# lilygo-surf-v1.net
KiCad netlist of a schematic drawn in EAGLE
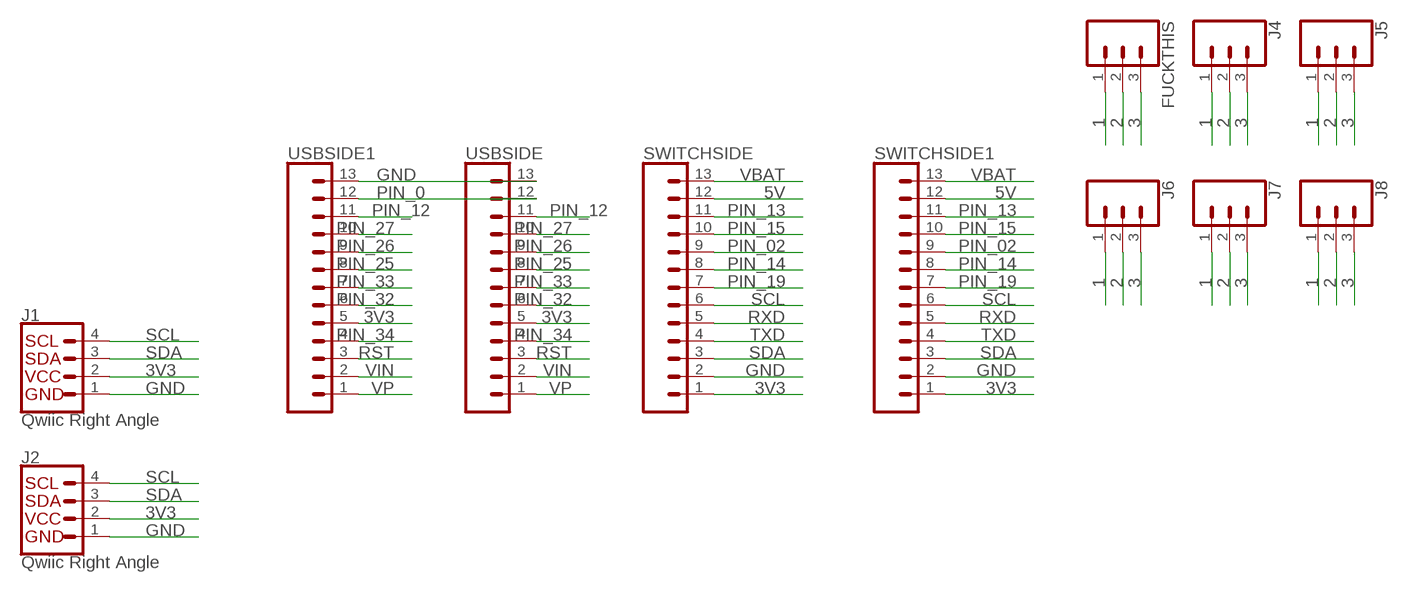
[diagram p0: schematic, sheet 1]

(export (version "E")
  (design (tool "Eeschema 10.0.6"))
  (components
    (comp (ref "FUCKTHIS")
      (value "CONN_03")
      (footprint "eagle-import:1X03")
      (libsource (lib "eagle-import") (part "CONN_03"))
    )
    (comp (ref "J1")
      (value "Qwiic Right Angle")
      (footprint "eagle-import:1X04_1MM_RA")
      (libsource (lib "eagle-import") (part "I2C_STANDARDQWIIC"))
    )
    (comp (ref "J2")
      (value "Qwiic Right Angle")
      (footprint "eagle-import:1X04_1MM_RA")
      (libsource (lib "eagle-import") (part "I2C_STANDARDQWIIC"))
    )
    (comp (ref "J4")
      (value "CONN_03")
      (footprint "eagle-import:1X03")
      (libsource (lib "eagle-import") (part "CONN_03"))
    )
    (comp (ref "J5")
      (value "CONN_03")
      (footprint "eagle-import:1X03")
      (libsource (lib "eagle-import") (part "CONN_03"))
    )
    (comp (ref "J6")
      (value "CONN_03")
      (footprint "eagle-import:1X03")
      (libsource (lib "eagle-import") (part "CONN_03"))
    )
    (comp (ref "J7")
      (value "CONN_03")
      (footprint "eagle-import:1X03")
      (libsource (lib "eagle-import") (part "CONN_03"))
    )
    (comp (ref "J8")
      (value "CONN_03")
      (footprint "eagle-import:1X03")
      (libsource (lib "eagle-import") (part "CONN_03"))
    )
    (comp (ref "SWITCHSIDE")
      (value "CONN_13LOCK")
      (footprint "eagle-import:1X13_LOCK")
      (libsource (lib "eagle-import") (part "CONN_13LOCK"))
    )
    (comp (ref "SWITCHSIDE1")
      (value "CONN_13LOCK")
      (footprint "eagle-import:1X13_LOCK")
      (libsource (lib "eagle-import") (part "CONN_13LOCK"))
    )
    (comp (ref "USBSIDE")
      (value "CONN_13LOCK")
      (footprint "eagle-import:1X13_LOCK")
      (libsource (lib "eagle-import") (part "CONN_13LOCK"))
    )
    (comp (ref "USBSIDE1")
      (value "CONN_13LOCK")
      (footprint "eagle-import:1X13_LOCK")
      (libsource (lib "eagle-import") (part "CONN_13LOCK"))
    )
  )
  (nets
    (net (code "1") (name "/1") (class "Default")
      (node (ref "FUCKTHIS") (pin "1") (pinfunction "1_1") (pintype "passive"))
      (node (ref "J4") (pin "1") (pinfunction "1_1") (pintype "passive"))
      (node (ref "J5") (pin "1") (pinfunction "1_1") (pintype "passive"))
      (node (ref "J6") (pin "1") (pinfunction "1_1") (pintype "passive"))
      (node (ref "J7") (pin "1") (pinfunction "1_1") (pintype "passive"))
      (node (ref "J8") (pin "1") (pinfunction "1_1") (pintype "passive"))
    )
    (net (code "2") (name "/2") (class "Default")
      (node (ref "FUCKTHIS") (pin "2") (pinfunction "2_2") (pintype "passive"))
      (node (ref "J4") (pin "2") (pinfunction "2_2") (pintype "passive"))
      (node (ref "J5") (pin "2") (pinfunction "2_2") (pintype "passive"))
      (node (ref "J6") (pin "2") (pinfunction "2_2") (pintype "passive"))
      (node (ref "J7") (pin "2") (pinfunction "2_2") (pintype "passive"))
      (node (ref "J8") (pin "2") (pinfunction "2_2") (pintype "passive"))
    )
    (net (code "3") (name "/3") (class "Default")
      (node (ref "FUCKTHIS") (pin "3") (pinfunction "3_3") (pintype "passive"))
      (node (ref "J4") (pin "3") (pinfunction "3_3") (pintype "passive"))
      (node (ref "J5") (pin "3") (pinfunction "3_3") (pintype "passive"))
      (node (ref "J6") (pin "3") (pinfunction "3_3") (pintype "passive"))
      (node (ref "J7") (pin "3") (pinfunction "3_3") (pintype "passive"))
      (node (ref "J8") (pin "3") (pinfunction "3_3") (pintype "passive"))
    )
    (net (code "4") (name "/3V3") (class "Default")
      (node (ref "J1") (pin "2") (pinfunction "2_2") (pintype "power_in"))
      (node (ref "J2") (pin "2") (pinfunction "2_2") (pintype "power_in"))
      (node (ref "SWITCHSIDE") (pin "1") (pinfunction "1_1") (pintype "passive"))
      (node (ref "SWITCHSIDE1") (pin "1") (pinfunction "1_1") (pintype "passive"))
      (node (ref "USBSIDE") (pin "5") (pinfunction "5_5") (pintype "passive"))
      (node (ref "USBSIDE1") (pin "5") (pinfunction "5_5") (pintype "passive"))
    )
    (net (code "5") (name "/5V") (class "Default")
      (node (ref "SWITCHSIDE") (pin "12") (pinfunction "12_12") (pintype "passive"))
      (node (ref "SWITCHSIDE1") (pin "12") (pinfunction "12_12") (pintype "passive"))
    )
    (net (code "6") (name "/GND") (class "Default")
      (node (ref "J1") (pin "1") (pinfunction "1_1") (pintype "power_in"))
      (node (ref "J2") (pin "1") (pinfunction "1_1") (pintype "power_in"))
      (node (ref "SWITCHSIDE") (pin "2") (pinfunction "2_2") (pintype "passive"))
      (node (ref "SWITCHSIDE1") (pin "2") (pinfunction "2_2") (pintype "passive"))
      (node (ref "USBSIDE") (pin "13") (pinfunction "13_13") (pintype "passive"))
      (node (ref "USBSIDE1") (pin "13") (pinfunction "13_13") (pintype "passive"))
    )
    (net (code "7") (name "/PIN_0") (class "Default")
      (node (ref "USBSIDE") (pin "12") (pinfunction "12_12") (pintype "passive"))
      (node (ref "USBSIDE1") (pin "12") (pinfunction "12_12") (pintype "passive"))
    )
    (net (code "8") (name "/PIN_02") (class "Default")
      (node (ref "SWITCHSIDE") (pin "9") (pinfunction "9_9") (pintype "passive"))
      (node (ref "SWITCHSIDE1") (pin "9") (pinfunction "9_9") (pintype "passive"))
    )
    (net (code "9") (name "/PIN_12") (class "Default")
      (node (ref "USBSIDE") (pin "11") (pinfunction "11_11") (pintype "passive"))
      (node (ref "USBSIDE1") (pin "11") (pinfunction "11_11") (pintype "passive"))
    )
    (net (code "10") (name "/PIN_13") (class "Default")
      (node (ref "SWITCHSIDE") (pin "11") (pinfunction "11_11") (pintype "passive"))
      (node (ref "SWITCHSIDE1") (pin "11") (pinfunction "11_11") (pintype "passive"))
    )
    (net (code "11") (name "/PIN_14") (class "Default")
      (node (ref "SWITCHSIDE") (pin "8") (pinfunction "8_8") (pintype "passive"))
      (node (ref "SWITCHSIDE1") (pin "8") (pinfunction "8_8") (pintype "passive"))
    )
    (net (code "12") (name "/PIN_15") (class "Default")
      (node (ref "SWITCHSIDE") (pin "10") (pinfunction "10_10") (pintype "passive"))
      (node (ref "SWITCHSIDE1") (pin "10") (pinfunction "10_10") (pintype "passive"))
    )
    (net (code "13") (name "/PIN_19") (class "Default")
      (node (ref "SWITCHSIDE") (pin "7") (pinfunction "7_7") (pintype "passive"))
      (node (ref "SWITCHSIDE1") (pin "7") (pinfunction "7_7") (pintype "passive"))
    )
    (net (code "14") (name "/PIN_25") (class "Default")
      (node (ref "USBSIDE") (pin "8") (pinfunction "8_8") (pintype "passive"))
      (node (ref "USBSIDE1") (pin "8") (pinfunction "8_8") (pintype "passive"))
    )
    (net (code "15") (name "/PIN_26") (class "Default")
      (node (ref "USBSIDE") (pin "9") (pinfunction "9_9") (pintype "passive"))
      (node (ref "USBSIDE1") (pin "9") (pinfunction "9_9") (pintype "passive"))
    )
    (net (code "16") (name "/PIN_27") (class "Default")
      (node (ref "USBSIDE") (pin "10") (pinfunction "10_10") (pintype "passive"))
      (node (ref "USBSIDE1") (pin "10") (pinfunction "10_10") (pintype "passive"))
    )
    (net (code "17") (name "/PIN_32") (class "Default")
      (node (ref "USBSIDE") (pin "6") (pinfunction "6_6") (pintype "passive"))
      (node (ref "USBSIDE1") (pin "6") (pinfunction "6_6") (pintype "passive"))
    )
    (net (code "18") (name "/PIN_33") (class "Default")
      (node (ref "USBSIDE") (pin "7") (pinfunction "7_7") (pintype "passive"))
      (node (ref "USBSIDE1") (pin "7") (pinfunction "7_7") (pintype "passive"))
    )
    (net (code "19") (name "/PIN_34") (class "Default")
      (node (ref "USBSIDE") (pin "4") (pinfunction "4_4") (pintype "passive"))
      (node (ref "USBSIDE1") (pin "4") (pinfunction "4_4") (pintype "passive"))
    )
    (net (code "20") (name "/RST") (class "Default")
      (node (ref "USBSIDE") (pin "3") (pinfunction "3_3") (pintype "passive"))
      (node (ref "USBSIDE1") (pin "3") (pinfunction "3_3") (pintype "passive"))
    )
    (net (code "21") (name "/RXD") (class "Default")
      (node (ref "SWITCHSIDE") (pin "5") (pinfunction "5_5") (pintype "passive"))
      (node (ref "SWITCHSIDE1") (pin "5") (pinfunction "5_5") (pintype "passive"))
    )
    (net (code "22") (name "/SCL") (class "Default")
      (node (ref "J1") (pin "4") (pinfunction "4_4") (pintype "passive"))
      (node (ref "J2") (pin "4") (pinfunction "4_4") (pintype "passive"))
      (node (ref "SWITCHSIDE") (pin "6") (pinfunction "6_6") (pintype "passive"))
      (node (ref "SWITCHSIDE1") (pin "6") (pinfunction "6_6") (pintype "passive"))
    )
    (net (code "23") (name "/SDA") (class "Default")
      (node (ref "J1") (pin "3") (pinfunction "3_3") (pintype "passive"))
      (node (ref "J2") (pin "3") (pinfunction "3_3") (pintype "passive"))
      (node (ref "SWITCHSIDE") (pin "3") (pinfunction "3_3") (pintype "passive"))
      (node (ref "SWITCHSIDE1") (pin "3") (pinfunction "3_3") (pintype "passive"))
    )
    (net (code "24") (name "/TXD") (class "Default")
      (node (ref "SWITCHSIDE") (pin "4") (pinfunction "4_4") (pintype "passive"))
      (node (ref "SWITCHSIDE1") (pin "4") (pinfunction "4_4") (pintype "passive"))
    )
    (net (code "25") (name "/VBAT") (class "Default")
      (node (ref "SWITCHSIDE") (pin "13") (pinfunction "13_13") (pintype "passive"))
      (node (ref "SWITCHSIDE1") (pin "13") (pinfunction "13_13") (pintype "passive"))
    )
    (net (code "26") (name "/VIN") (class "Default")
      (node (ref "USBSIDE") (pin "2") (pinfunction "2_2") (pintype "passive"))
      (node (ref "USBSIDE1") (pin "2") (pinfunction "2_2") (pintype "passive"))
    )
    (net (code "27") (name "/VP") (class "Default")
      (node (ref "USBSIDE") (pin "1") (pinfunction "1_1") (pintype "passive"))
      (node (ref "USBSIDE1") (pin "1") (pinfunction "1_1") (pintype "passive"))
    )
  )
)
